# angel.net
KiCad netlist of a schematic drawn in EAGLE
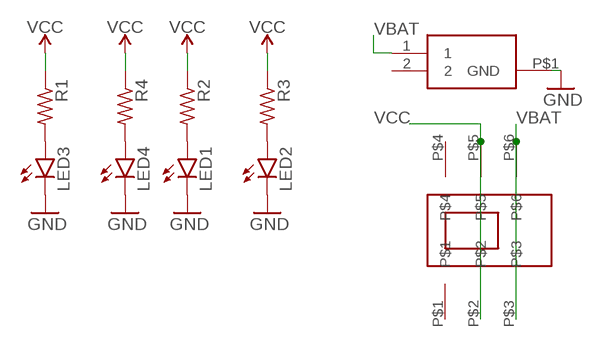
[diagram p0: schematic, sheet 1]

(export (version "E")
  (design (tool "Eeschema 10.0.6"))
  (components
    (comp (ref "LED1")
      (value "LEDCHIP-LED0805")
      (footprint "eagle-import:CHIP-LED0805")
      (libsource (lib "eagle-import") (part "LEDCHIP-LED0805"))
    )
    (comp (ref "LED2")
      (value "LEDCHIP-LED0805")
      (footprint "eagle-import:CHIP-LED0805")
      (libsource (lib "eagle-import") (part "LEDCHIP-LED0805"))
    )
    (comp (ref "LED3")
      (value "LEDCHIP-LED0805")
      (footprint "eagle-import:CHIP-LED0805")
      (libsource (lib "eagle-import") (part "LEDCHIP-LED0805"))
    )
    (comp (ref "LED4")
      (value "LEDCHIP-LED0805")
      (footprint "eagle-import:CHIP-LED0805")
      (libsource (lib "eagle-import") (part "LEDCHIP-LED0805"))
    )
    (comp (ref "R1")
      (value "R-US_R0603")
      (footprint "eagle-import:R0603")
      (libsource (lib "eagle-import") (part "R-US_R0603"))
    )
    (comp (ref "R2")
      (value "R-US_R0603")
      (footprint "eagle-import:R0603")
      (libsource (lib "eagle-import") (part "R-US_R0603"))
    )
    (comp (ref "R3")
      (value "R-US_R0603")
      (footprint "eagle-import:R0603")
      (libsource (lib "eagle-import") (part "R-US_R0603"))
    )
    (comp (ref "R4")
      (value "R-US_R0603")
      (footprint "eagle-import:R0603")
      (libsource (lib "eagle-import") (part "R-US_R0603"))
    )
    (comp (ref "U$1")
      (value "CL-SB-22A-02T-SLIDE-SWITCH-TUCKED-PADS")
      (footprint "eagle-import:CL-SB-22A-02T-DPDT-COMPACT-SWITCH")
      (libsource (lib "eagle-import") (part "CL-SB-22A-02T-SLIDE-SWITCH-TUCKED-PADS"))
    )
    (comp (ref "VBAT")
      (value "BAT-HLD-012-SMT")
      (footprint "eagle-import:BATHLD012SMT")
      (fields (field (name "MOUSER_PART_NUMBER") "712-BAT-HLD-012-SMT"))
      (libsource (lib "eagle-import") (part "BAT-HLD-012-SMT"))
    )
  )
  (nets
    (net (code "1") (name "/VBAT") (class "Default")
      (node (ref "U$1") (pin "P$3") (pinfunction "P$3_P$3") (pintype "bidirectional"))
      (node (ref "U$1") (pin "P$6") (pinfunction "P$6_P$6") (pintype "bidirectional"))
      (node (ref "VBAT") (pin "1") (pinfunction "1_1") (pintype "bidirectional"))
    )
    (net (code "2") (name "GND") (class "Default")
      (node (ref "LED1") (pin "C") (pinfunction "C_C") (pintype "passive"))
      (node (ref "LED2") (pin "C") (pinfunction "C_C") (pintype "passive"))
      (node (ref "LED3") (pin "C") (pinfunction "C_C") (pintype "passive"))
      (node (ref "LED4") (pin "C") (pinfunction "C_C") (pintype "passive"))
      (node (ref "VBAT") (pin "P$1") (pinfunction "GND_P$1") (pintype "bidirectional"))
    )
    (net (code "3") (name "Net-(LED1-PadA)") (class "Default")
      (node (ref "LED1") (pin "A") (pinfunction "A_A") (pintype "passive"))
      (node (ref "R2") (pin "2") (pinfunction "2_2") (pintype "passive"))
    )
    (net (code "4") (name "Net-(LED2-PadA)") (class "Default")
      (node (ref "LED2") (pin "A") (pinfunction "A_A") (pintype "passive"))
      (node (ref "R3") (pin "2") (pinfunction "2_2") (pintype "passive"))
    )
    (net (code "5") (name "Net-(LED3-PadA)") (class "Default")
      (node (ref "LED3") (pin "A") (pinfunction "A_A") (pintype "passive"))
      (node (ref "R1") (pin "2") (pinfunction "2_2") (pintype "passive"))
    )
    (net (code "6") (name "Net-(LED4-PadA)") (class "Default")
      (node (ref "LED4") (pin "A") (pinfunction "A_A") (pintype "passive"))
      (node (ref "R4") (pin "2") (pinfunction "2_2") (pintype "passive"))
    )
    (net (code "7") (name "VCC") (class "Default")
      (node (ref "R1") (pin "1") (pinfunction "1_1") (pintype "passive"))
      (node (ref "R2") (pin "1") (pinfunction "1_1") (pintype "passive"))
      (node (ref "R3") (pin "1") (pinfunction "1_1") (pintype "passive"))
      (node (ref "R4") (pin "1") (pinfunction "1_1") (pintype "passive"))
      (node (ref "U$1") (pin "P$2") (pinfunction "P$2_P$2") (pintype "bidirectional"))
      (node (ref "U$1") (pin "P$5") (pinfunction "P$5_P$5") (pintype "bidirectional"))
    )
    (net (code "8") (name "unconnected-(U$1-PadP$1)") (class "Default")
      (node (ref "U$1") (pin "P$1") (pinfunction "P$1_P$1") (pintype "bidirectional"))
    )
    (net (code "9") (name "unconnected-(U$1-PadP$4)") (class "Default")
      (node (ref "U$1") (pin "P$4") (pinfunction "P$4_P$4") (pintype "bidirectional"))
    )
    (net (code "10") (name "unconnected-(VBAT-Pad2)") (class "Default")
      (node (ref "VBAT") (pin "2") (pinfunction "2_2") (pintype "bidirectional"))
    )
  )
)
